# SolarPCB.net
KiCad netlist of a schematic drawn in Altium Designer
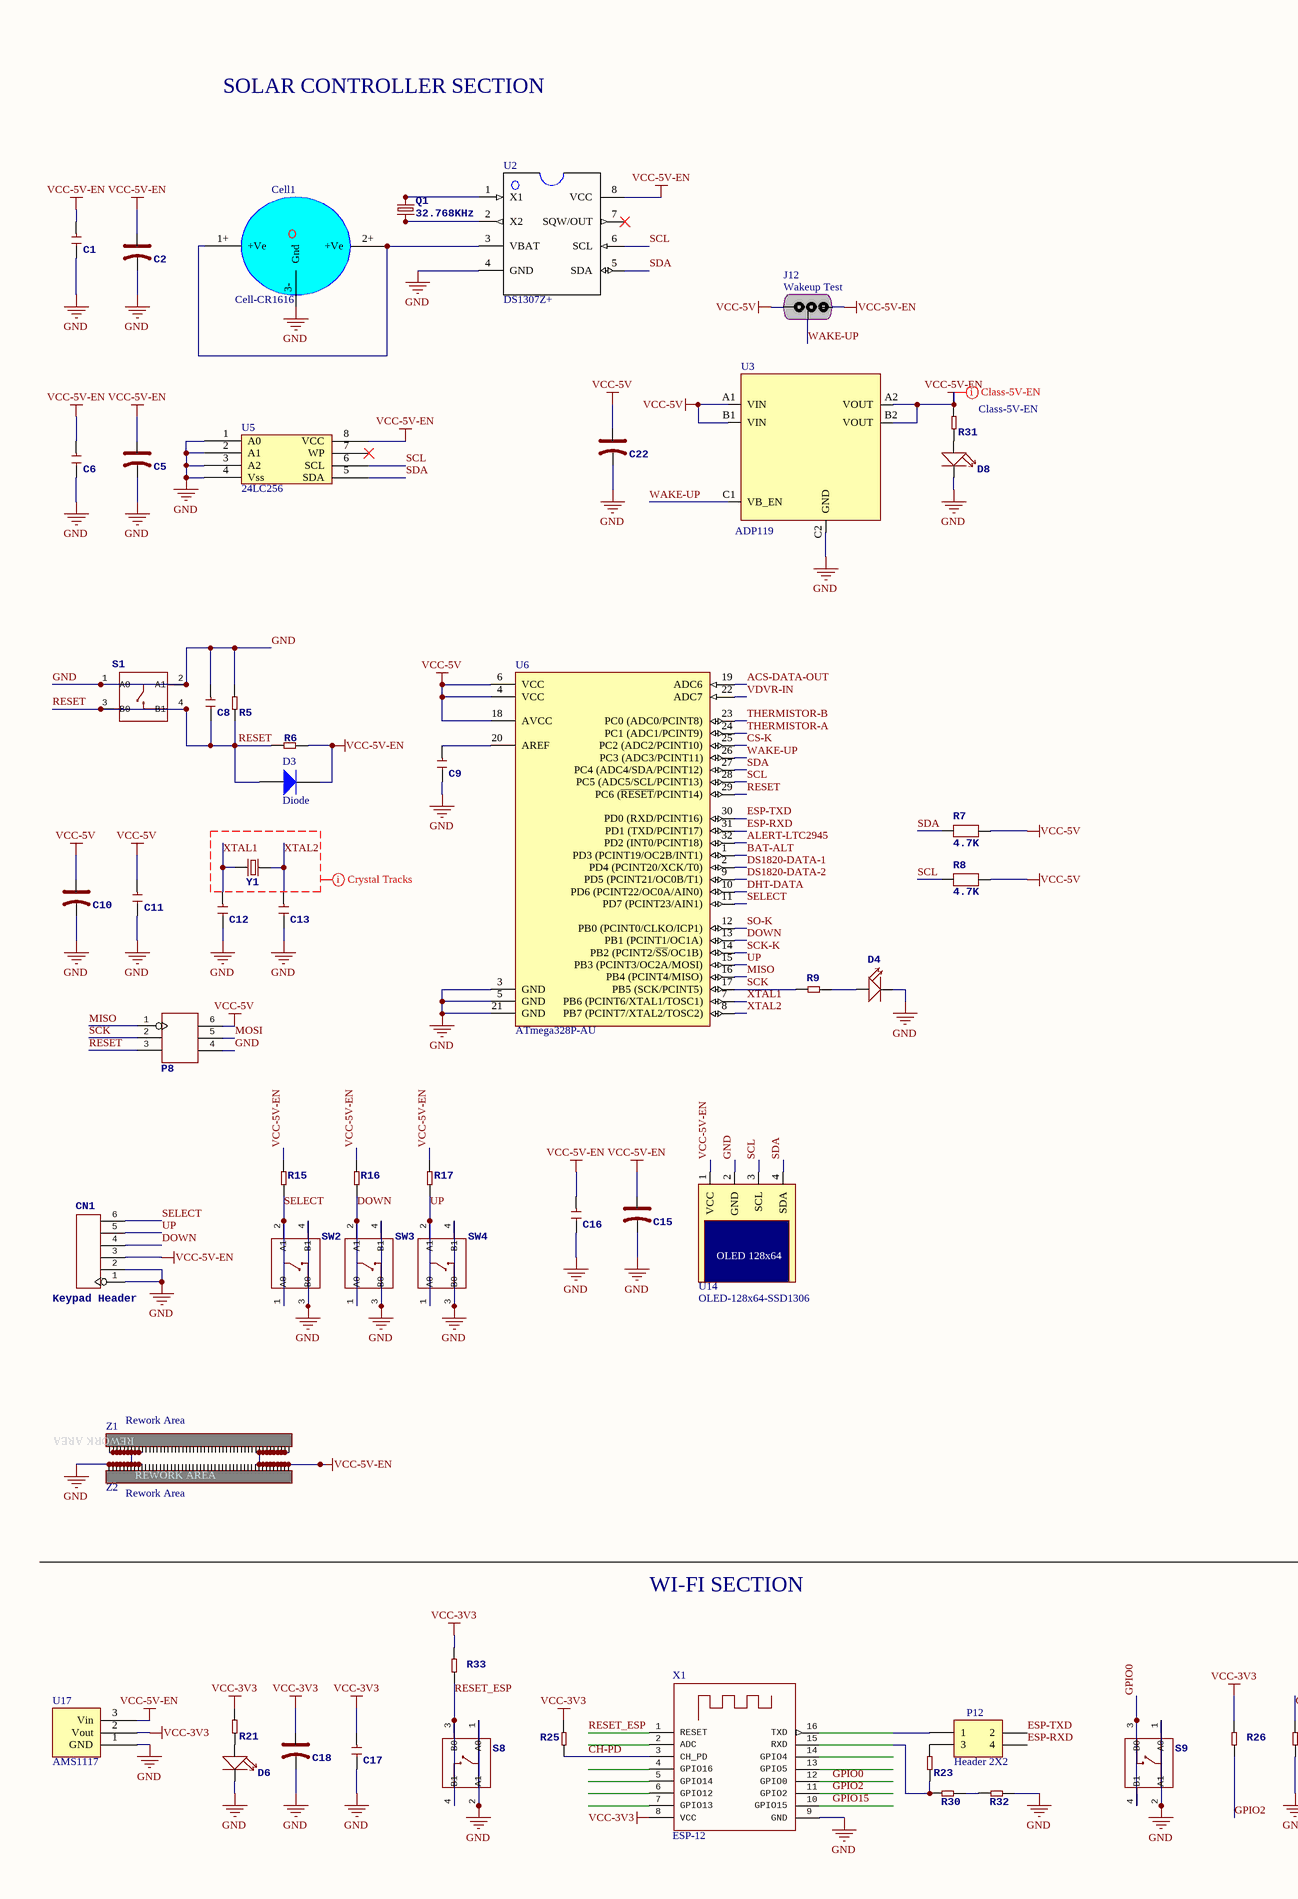
[diagram p0: SolarPCB.SchDoc, left]
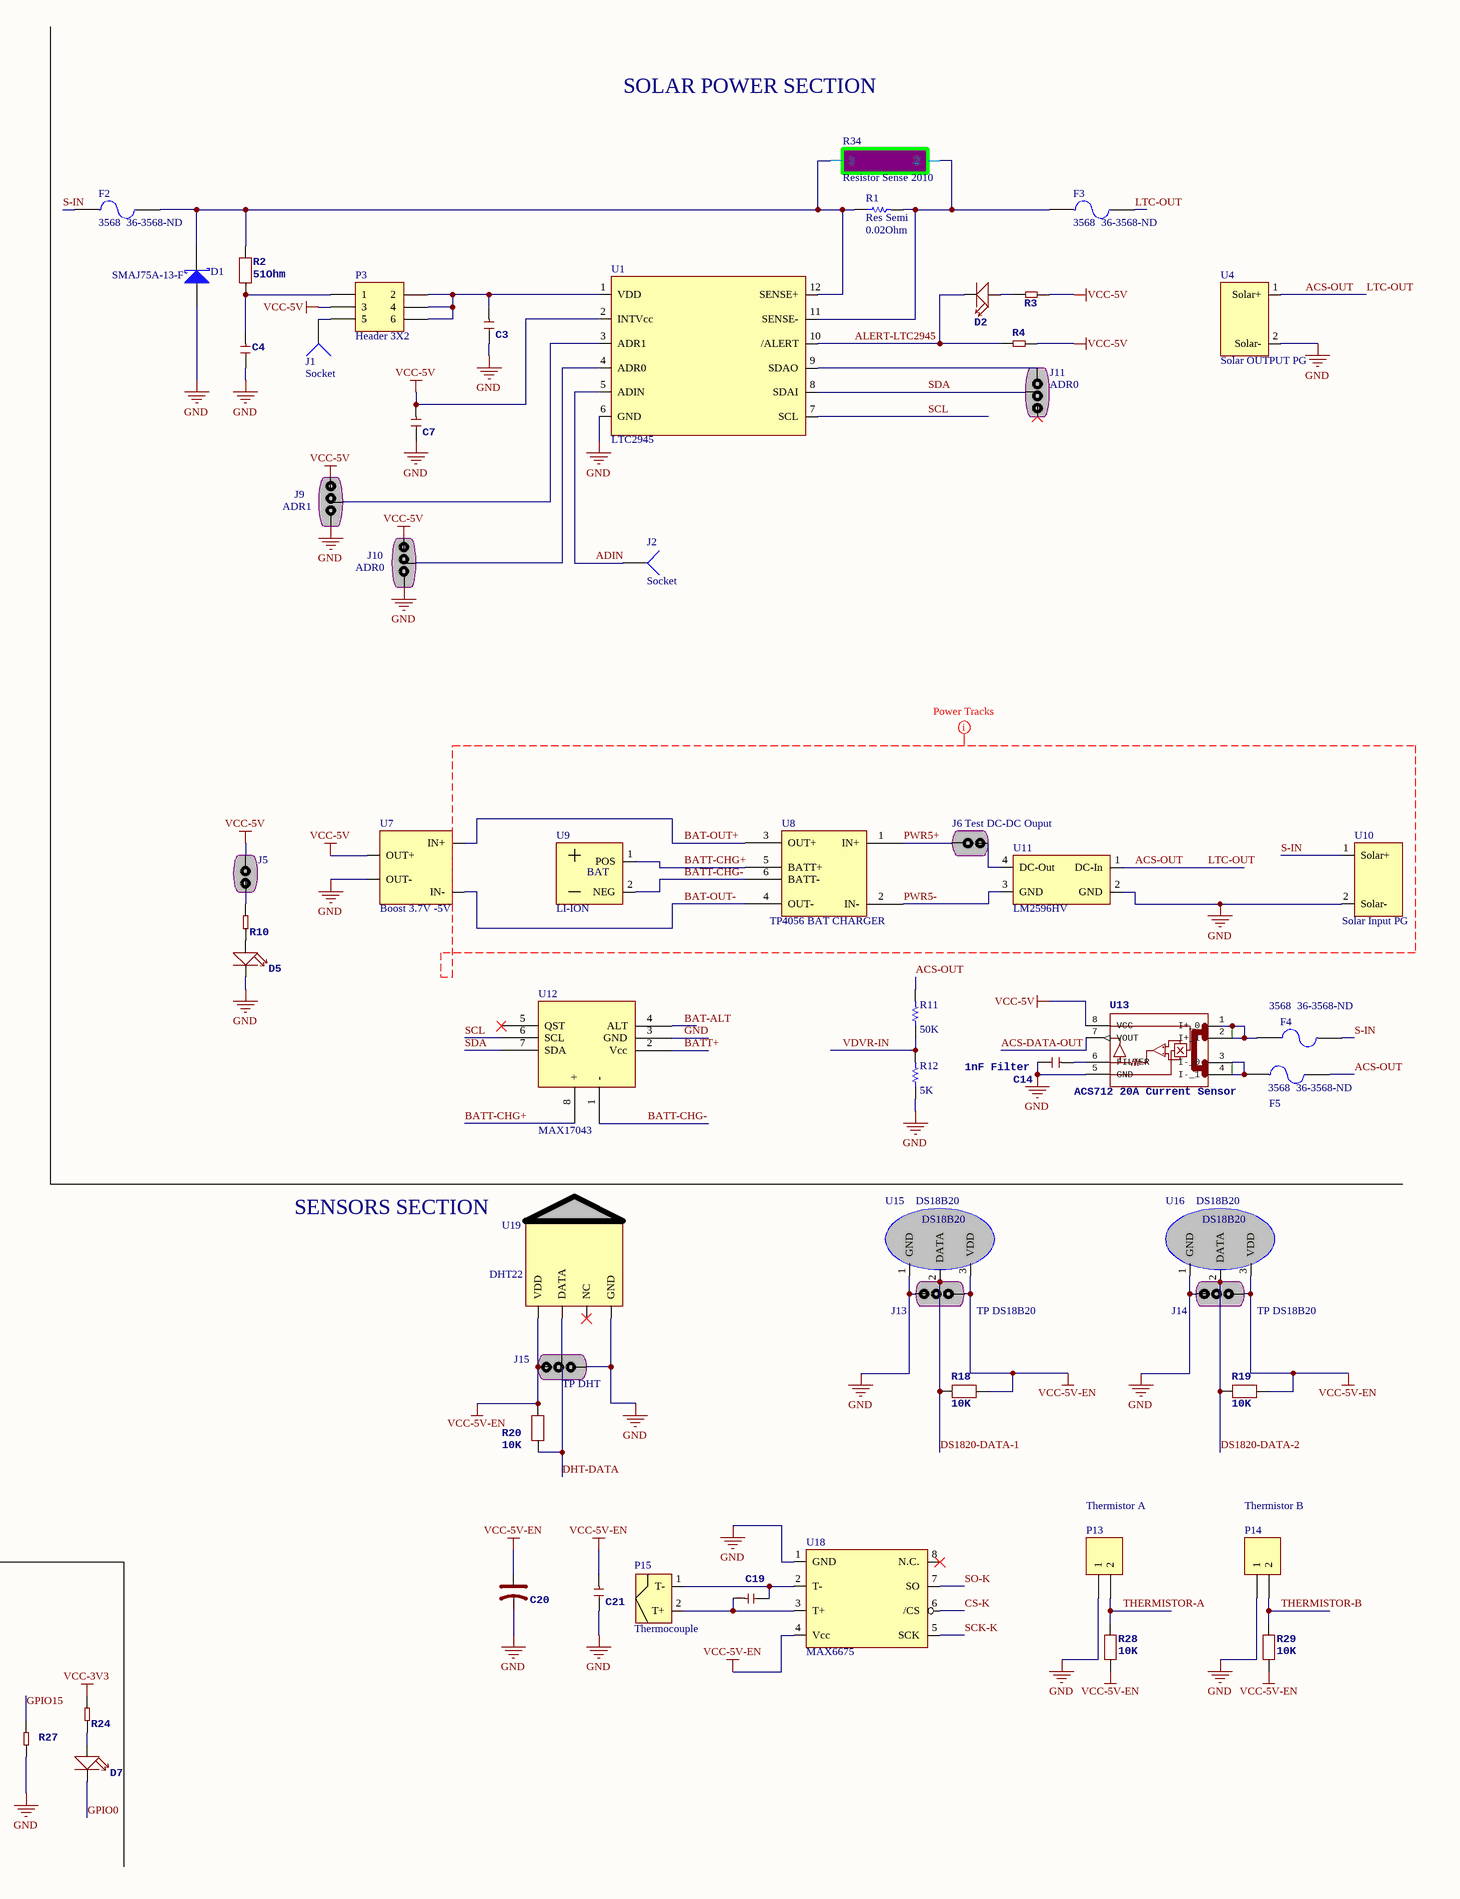
[diagram p1: SolarPCB.SchDoc, right]

(export (version "E")
  (design (tool "Eeschema 10.0.6"))
  (components
    (comp (ref "C1")
      (value "302010165")
      (footprint "C0805")
      (description "100nF")
      (fields (field (name "MPN") "CC0805KRX7R9BB104"))
      (libsource (lib "Seeed-Capacitor") (part "CERAMIC-100NF-50V-10%-X7R(0805)"))
    )
    (comp (ref "C2")
      (value "302020002")
      (footprint "AVX-A")
      (description "10uF Cap Decoupling 16V")
      (fields (field (name "MPN") "TAJA106K016RNJ"))
      (libsource (lib "Seeed-Capacitor") (part "TANTALUM-SMD-10UF-16V-10%(AVX-A)"))
    )
    (comp (ref "C3")
      (value "302010165")
      (footprint "C0805")
      (description "100nF")
      (fields (field (name "MPN") "CC0805KRX7R9BB104"))
      (libsource (lib "Seeed-Capacitor") (part "CERAMIC-100NF-50V-10%-X7R(0805)"))
    )
    (comp (ref "C4")
      (value "302010189")
      (footprint "C1206")
      (fields (field (name "MPN") "CC1206KKX7RCBB102"))
      (libsource (lib "Seeed-Capacitor") (part "CERAMIC-1NF-1KV-10%-X7R?(1206)"))
    )
    (comp (ref "C5")
      (value "302020002")
      (footprint "AVX-A")
      (description "10uF Cap Decoupling 16V")
      (fields (field (name "MPN") "TAJA106K016RNJ"))
      (libsource (lib "Seeed-Capacitor") (part "TANTALUM-SMD-10UF-16V-10%(AVX-A)"))
    )
    (comp (ref "C6")
      (value "302010165")
      (footprint "C0805")
      (description "100nF")
      (fields (field (name "MPN") "CC0805KRX7R9BB104"))
      (libsource (lib "Seeed-Capacitor") (part "CERAMIC-100NF-50V-10%-X7R(0805)"))
    )
    (comp (ref "C7")
      (value "302010165")
      (footprint "C0805")
      (description "100nF")
      (fields (field (name "MPN") "CC0805KRX7R9BB104"))
      (libsource (lib "Seeed-Capacitor") (part "CERAMIC-100NF-50V-10%-X7R(0805)"))
    )
    (comp (ref "C8")
      (value "302010165")
      (footprint "C0805")
      (description "100nF")
      (fields (field (name "MPN") "CC0805KRX7R9BB104"))
      (libsource (lib "Seeed-Capacitor") (part "CERAMIC-100NF-50V-10%-X7R(0805)"))
    )
    (comp (ref "C9")
      (value "302010165")
      (footprint "C0805")
      (description "100nF")
      (fields (field (name "MPN") "CC0805KRX7R9BB104"))
      (libsource (lib "Seeed-Capacitor") (part "CERAMIC-100NF-50V-10%-X7R(0805)"))
    )
    (comp (ref "C10")
      (value "302020002")
      (footprint "AVX-A")
      (description "10uF Cap Decoupling 16V")
      (fields (field (name "MPN") "TAJA106K016RNJ"))
      (libsource (lib "Seeed-Capacitor") (part "TANTALUM-SMD-10UF-16V-10%(AVX-A)"))
    )
    (comp (ref "C11")
      (value "302010165")
      (footprint "C0805")
      (description "100nF")
      (fields (field (name "MPN") "CC0805KRX7R9BB104"))
      (libsource (lib "Seeed-Capacitor") (part "CERAMIC-100NF-50V-10%-X7R(0805)"))
    )
    (comp (ref "C12")
      (value "302010018")
      (footprint "C0805")
      (fields (field (name "MPN") "CC0402JRNPO9BN220"))
      (libsource (lib "Seeed-Capacitor") (part "CERAMIC-22PF-50V-5%-NPO(0402)"))
    )
    (comp (ref "C13")
      (value "302010018")
      (footprint "C0805")
      (fields (field (name "MPN") "CC0402JRNPO9BN220"))
      (libsource (lib "Seeed-Capacitor") (part "CERAMIC-22PF-50V-5%-NPO(0402)"))
    )
    (comp (ref "C14")
      (value "1nF Filter")
      (footprint "C0805")
      (description "1nF Filter Cap as per Datasheet")
      (fields (field (name "MPN") "CC0402KRX7R8BB104"))
      (libsource (lib "Seeed-Capacitor") (part "CERAMIC-100NF-25V-10%-X7R(0402)"))
    )
    (comp (ref "C15")
      (value "302020002")
      (footprint "AVX-A")
      (description "10uF Cap Decoupling 16V")
      (fields (field (name "MPN") "TAJA106K016RNJ"))
      (libsource (lib "Seeed-Capacitor") (part "TANTALUM-SMD-10UF-16V-10%(AVX-A)"))
    )
    (comp (ref "C16")
      (value "302010165")
      (footprint "C0805")
      (description "100nF")
      (fields (field (name "MPN") "CC0805KRX7R9BB104"))
      (libsource (lib "Seeed-Capacitor") (part "CERAMIC-100NF-50V-10%-X7R(0805)"))
    )
    (comp (ref "C17")
      (value "302010165")
      (footprint "C0805")
      (description "100nF")
      (fields (field (name "MPN") "CC0805KRX7R9BB104"))
      (libsource (lib "Seeed-Capacitor") (part "CERAMIC-100NF-50V-10%-X7R(0805)"))
    )
    (comp (ref "C18")
      (value "302020002")
      (footprint "AVX-A")
      (description "10uF Cap Decoupling 16V")
      (fields (field (name "MPN") "TAJA106K016RNJ"))
      (libsource (lib "Seeed-Capacitor") (part "TANTALUM-SMD-10UF-16V-10%(AVX-A)"))
    )
    (comp (ref "C19")
      (value "302010175")
      (footprint "C0805")
      (fields (field (name "MPN") "CC0805JRX7R9BB103"))
      (libsource (lib "Seeed-Capacitor") (part "CERAMIC-10NF-50V-5%-X7R(0805)"))
    )
    (comp (ref "C20")
      (value "302020002")
      (footprint "AVX-A")
      (description "10uF Cap Decoupling 16V")
      (fields (field (name "MPN") "TAJA106K016RNJ"))
      (libsource (lib "Seeed-Capacitor") (part "TANTALUM-SMD-10UF-16V-10%(AVX-A)"))
    )
    (comp (ref "C21")
      (value "302010165")
      (footprint "C0805")
      (description "100nF")
      (fields (field (name "MPN") "CC0805KRX7R9BB104"))
      (libsource (lib "Seeed-Capacitor") (part "CERAMIC-100NF-50V-10%-X7R(0805)"))
    )
    (comp (ref "C22")
      (value "302020002")
      (footprint "AVX-A")
      (description "10uF Cap Decoupling 16V")
      (fields (field (name "MPN") "TAJA106K016RNJ"))
      (libsource (lib "Seeed-Capacitor") (part "TANTALUM-SMD-10UF-16V-10%(AVX-A)"))
    )
    (comp (ref "Cell1")
      (value "Cell-CR1616")
      (footprint "CellCR1616")
      (libsource (lib "Schlib_HAS_1.0") (part "Cell-CR1616"))
    )
    (comp (ref "CN1")
      (value "Keypad Header")
      (footprint "H6-2.54")
      (fields (field (name "MPN") "F185-1106A1BSYC1"))
      (libsource (lib "Seeed-Connector") (part "DIP-BLACK-FEMALE-HEADER-VERT(6P-2.54)"))
    )
    (comp (ref "D1")
      (value "SMAJ75A-13-F")
      (footprint "SMAJ5.0-TVS")
      (description "SMA")
      (fields (field (name "PUBLISHER") "Altium Limited"))
      (libsource (lib "Miscellaneous Devices") (part "D Schottky"))
    )
    (comp (ref "D2")
      (value "304090046")
      (footprint "LED-0805")
      (fields (field (name "MPN") "17-215SURC/S530-A2/TR8"))
      (libsource (lib "Seeed-LED") (part "SMD-LED-CLEAR-RED(0805)"))
    )
    (comp (ref "D3")
      (value "Diode")
      (footprint "1206 Diode SMD")
      (description "Default Diode")
      (fields (field (name "PUBLISHER") "Altium Limited"))
      (libsource (lib "Miscellaneous Devices") (part "Diode"))
    )
    (comp (ref "D4")
      (value "304090046")
      (footprint "LED-0805")
      (fields (field (name "MPN") "17-215SURC/S530-A2/TR8"))
      (libsource (lib "Seeed-LED") (part "SMD-LED-CLEAR-RED(0805)"))
    )
    (comp (ref "D5")
      (value "304090046")
      (footprint "LED-0805")
      (fields (field (name "MPN") "17-215SURC/S530-A2/TR8"))
      (libsource (lib "Seeed-LED") (part "SMD-LED-CLEAR-RED(0805)"))
    )
    (comp (ref "D6")
      (value "304090046")
      (footprint "LED-0805")
      (fields (field (name "MPN") "17-215SURC/S530-A2/TR8"))
      (libsource (lib "Seeed-LED") (part "SMD-LED-CLEAR-RED(0805)"))
    )
    (comp (ref "D7")
      (value "304090046")
      (footprint "LED-0805")
      (fields (field (name "MPN") "17-215SURC/S530-A2/TR8"))
      (libsource (lib "Seeed-LED") (part "SMD-LED-CLEAR-RED(0805)"))
    )
    (comp (ref "D8")
      (value "304090046")
      (footprint "LED-0805")
      (fields (field (name "MPN") "17-215SURC/S530-A2/TR8"))
      (libsource (lib "Seeed-LED") (part "SMD-LED-CLEAR-RED(0805)"))
    )
    (comp (ref "F2")
      (value "3568  36-3568-ND")
      (footprint "Fuse Holder Mini BLADE ATC")
      (description "3568  36-3568-ND FUSE HOLDER")
      (fields (field (name "PUBLISHER") "Altium Limited"))
      (libsource (lib "Miscellaneous Devices") (part "Fuse 2"))
    )
    (comp (ref "F3")
      (value "3568  36-3568-ND")
      (footprint "Fuse Holder Mini BLADE ATC")
      (description "3568  36-3568-ND FUSE HOLDER")
      (fields (field (name "PUBLISHER") "Altium Limited"))
      (libsource (lib "Miscellaneous Devices") (part "Fuse 2"))
    )
    (comp (ref "F4")
      (value "3568  36-3568-ND")
      (footprint "Fuse Holder Mini BLADE ATC")
      (description "3568  36-3568-ND FUSE HOLDER")
      (fields (field (name "PUBLISHER") "Altium Limited"))
      (libsource (lib "Miscellaneous Devices") (part "Fuse 2"))
    )
    (comp (ref "F5")
      (value "3568  36-3568-ND")
      (footprint "Fuse Holder Mini BLADE ATC")
      (description "3568  36-3568-ND FUSE HOLDER")
      (fields (field (name "PUBLISHER") "Altium Limited"))
      (libsource (lib "Miscellaneous Devices") (part "Fuse 2"))
    )
    (comp (ref "J1")
      (value "Socket")
      (footprint "PIN1")
      (fields (field (name "PUBLISHER") "Altium Limited"))
      (libsource (lib "Miscellaneous Connectors") (part "Socket"))
    )
    (comp (ref "J2")
      (value "Socket")
      (footprint "PIN1")
      (fields (field (name "PUBLISHER") "Altium Limited"))
      (libsource (lib "Miscellaneous Connectors") (part "Socket"))
    )
    (comp (ref "J5")
      (value "Jumper 2Pin")
      (footprint "H2-2.54")
      (description "2.54, Pin header")
      (libsource (lib "Solar_Schlib1") (part "Jumper"))
    )
    (comp (ref "J6")
      (value "Test DC-DC Ouput")
      (footprint "H2-2.54")
      (description "2.54, Pin header")
      (libsource (lib "Solar_Schlib1") (part "Jumper"))
    )
    (comp (ref "J9")
      (value "ADR1")
      (footprint "H3-2.54")
      (description "2.54mm Pitch male header")
      (libsource (lib "Solar_Schlib1") (part "Jumper Select"))
    )
    (comp (ref "J10")
      (value "ADR0")
      (footprint "H3-2.54")
      (description "2.54mm Pitch male header")
      (libsource (lib "Solar_Schlib1") (part "Jumper Select"))
    )
    (comp (ref "J11")
      (value "ADR0")
      (footprint "H3-2.54")
      (description "2.54mm Pitch male header")
      (libsource (lib "Solar_Schlib1") (part "Jumper Select"))
    )
    (comp (ref "J12")
      (value "Wakeup Test")
      (footprint "H3-2.54")
      (description "2.54mm Pitch male header")
      (libsource (lib "Solar_Schlib1") (part "Jumper Select"))
    )
    (comp (ref "J13")
      (value "TP DS18B20")
      (footprint "H3-2.54")
      (description "2.54mm Pitch male header")
      (libsource (lib "Solar_Schlib1") (part "Jumper Select"))
    )
    (comp (ref "J14")
      (value "TP DS18B20")
      (footprint "H3-2.54")
      (description "2.54mm Pitch male header")
      (libsource (lib "Solar_Schlib1") (part "Jumper Select"))
    )
    (comp (ref "J15")
      (value "TP DHT")
      (footprint "H3-2.54")
      (description "2.54mm Pitch male header")
      (libsource (lib "Solar_Schlib1") (part "Jumper Select"))
    )
    (comp (ref "P3")
      (value "Header 3X2")
      (footprint "HDR2X3")
      (description "Header, 3-Pin, Dual row")
      (fields (field (name "PUBLISHER") "Altium Limited"))
      (libsource (lib "Miscellaneous Connectors") (part "Header 3X2"))
    )
    (comp (ref "P8")
      (value "320020077")
      (footprint "HDR1X6")
      (fields (field (name "MPN") "P125-12A1BS116A1"))
      (libsource (lib "Seeed-Connector") (part "DIP-BLACK-MALE-HEADER(2X3P-2.54）-2.54"))
    )
    (comp (ref "P12")
      (value "Header 2X2")
      (footprint "HDR2X2")
      (description "Header, 2-Pin, Dual row")
      (fields (field (name "PUBLISHER") "Altium Limited"))
      (libsource (lib "Miscellaneous Connectors") (part "Header 2X2"))
    )
    (comp (ref "P13")
      (value "Thermistor A")
      (footprint "HDR1X2")
      (description "Header, 2-Pin")
      (fields (field (name "PUBLISHER") "Altium Limited"))
      (libsource (lib "Miscellaneous Connectors") (part "Header 2"))
    )
    (comp (ref "P14")
      (value "Thermistor B")
      (footprint "HDR1X2")
      (description "Header, 2-Pin")
      (fields (field (name "PUBLISHER") "Altium Limited"))
      (libsource (lib "Miscellaneous Connectors") (part "Header 2"))
    )
    (comp (ref "P15")
      (value "Thermocouple")
      (footprint "ScrewTerminal8.5")
      (description "K Type Termocouple")
      (libsource (lib "Solar_Schlib1") (part "ScrewTerminal8.5"))
    )
    (comp (ref "Q1")
      (value "32.768KHz")
      (footprint "RTC-XTAL")
      (libsource (lib "crystal") (part "CRYTALTC38H"))
    )
    (comp (ref "R1")
      (value "Res Semi")
      (footprint "AXIAL-0.5")
      (description "Semiconductor Resistor")
      (fields (field (name "ALTIUM_VALUE") "0.02Ohm") (field (name "PUBLISHER") "Altium Limited"))
      (libsource (lib "Miscellaneous Devices") (part "Res Semi"))
    )
    (comp (ref "R2")
      (value "51Ohm")
      (footprint "R0805")
      (libsource (lib "microbuilder") (part "RESISTOR0805_NOOUTLINE"))
    )
    (comp (ref "R3")
      (value "301010297")
      (footprint "R0603")
      (fields (field (name "MPN") "RC0603JR-07390RL"))
      (libsource (lib "Seeed-Resistor") (part "SMD-RES-390R-5%-1/10W(0603)"))
    )
    (comp (ref "R4")
      (value "301010361")
      (footprint "R0805")
      (description "10K")
      (fields (field (name "MPN") "RC0805FR-0710KL"))
      (libsource (lib "Seeed-Resistor") (part "SMD-RES-10K-1%-1/8W(0805)"))
    )
    (comp (ref "R5")
      (value "301010006")
      (footprint "R0402")
      (fields (field (name "MPN") "RC0402JR-071KL"))
      (libsource (lib "Seeed-Resistor") (part "SMD-RES-1K-5%-1/16W(0402)"))
    )
    (comp (ref "R6")
      (value "301010361")
      (footprint "R0805")
      (description "Pull up 10K resistor")
      (fields (field (name "MPN") "RC0805FR-0710KL"))
      (libsource (lib "Seeed-Resistor") (part "SMD-RES-10K-1%-1/8W(0805)"))
    )
    (comp (ref "R7")
      (value "4.7K")
      (footprint "R0805")
      (libsource (lib "microbuilder") (part "RESISTOR0805_NOOUTLINE"))
    )
    (comp (ref "R8")
      (value "4.7K")
      (footprint "R0805")
      (libsource (lib "microbuilder") (part "RESISTOR0805_NOOUTLINE"))
    )
    (comp (ref "R9")
      (value "301010297")
      (footprint "R0603")
      (fields (field (name "MPN") "RC0603JR-07390RL"))
      (libsource (lib "Seeed-Resistor") (part "SMD-RES-390R-5%-1/10W(0603)"))
    )
    (comp (ref "R10")
      (value "301010297")
      (footprint "R0603")
      (fields (field (name "MPN") "RC0603JR-07390RL"))
      (libsource (lib "Seeed-Resistor") (part "SMD-RES-390R-5%-1/10W(0603)"))
    )
    (comp (ref "R11")
      (value "50K")
      (footprint "AXIAL-0.3")
      (description "Resistor")
      (fields (field (name "PUBLISHER") "Altium Limited"))
      (libsource (lib "Miscellaneous Devices") (part "Res1"))
    )
    (comp (ref "R12")
      (value "5K")
      (footprint "AXIAL-0.3")
      (description "Resistor")
      (fields (field (name "PUBLISHER") "Altium Limited"))
      (libsource (lib "Miscellaneous Devices") (part "Res1"))
    )
    (comp (ref "R15")
      (value "301010361")
      (footprint "R0805")
      (description "Pull up 10K resistor for button")
      (fields (field (name "MPN") "RC0805FR-0710KL"))
      (libsource (lib "Seeed-Resistor") (part "SMD-RES-10K-1%-1/8W(0805)"))
    )
    (comp (ref "R16")
      (value "301010361")
      (footprint "R0805")
      (description "Pull up 10K resistor for button")
      (fields (field (name "MPN") "RC0805FR-0710KL"))
      (libsource (lib "Seeed-Resistor") (part "SMD-RES-10K-1%-1/8W(0805)"))
    )
    (comp (ref "R17")
      (value "301010361")
      (footprint "R0805")
      (description "Pull up 10K resistor for button")
      (fields (field (name "MPN") "RC0805FR-0710KL"))
      (libsource (lib "Seeed-Resistor") (part "SMD-RES-10K-1%-1/8W(0805)"))
    )
    (comp (ref "R18")
      (value "10K")
      (footprint "R0805")
      (libsource (lib "microbuilder") (part "RESISTOR0805_NOOUTLINE"))
    )
    (comp (ref "R19")
      (value "10K")
      (footprint "R0805")
      (libsource (lib "microbuilder") (part "RESISTOR0805_NOOUTLINE"))
    )
    (comp (ref "R20")
      (value "10K")
      (footprint "R0805")
      (libsource (lib "microbuilder") (part "RESISTOR0805_NOOUTLINE"))
    )
    (comp (ref "R21")
      (value "301010297")
      (footprint "R0603")
      (fields (field (name "MPN") "RC0603JR-07390RL"))
      (libsource (lib "Seeed-Resistor") (part "SMD-RES-390R-5%-1/10W(0603)"))
    )
    (comp (ref "R23")
      (value "301010311")
      (footprint "R0805")
      (fields (field (name "MPN") "RC0805JR-071KL"))
      (libsource (lib "Seeed-Resistor") (part "SMD-RES-1K-5%-1/8W(0805)"))
    )
    (comp (ref "R24")
      (value "301010297")
      (footprint "R0603")
      (fields (field (name "MPN") "RC0603JR-07390RL"))
      (libsource (lib "Seeed-Resistor") (part "SMD-RES-390R-5%-1/10W(0603)"))
    )
    (comp (ref "R25")
      (value "301010361")
      (footprint "R0805")
      (description "Pull up 10K resistor for button")
      (fields (field (name "MPN") "RC0805FR-0710KL"))
      (libsource (lib "Seeed-Resistor") (part "SMD-RES-10K-1%-1/8W(0805)"))
    )
    (comp (ref "R26")
      (value "301010361")
      (footprint "R0805")
      (description "Pull up 10K resistor for button")
      (fields (field (name "MPN") "RC0805FR-0710KL"))
      (libsource (lib "Seeed-Resistor") (part "SMD-RES-10K-1%-1/8W(0805)"))
    )
    (comp (ref "R27")
      (value "301010361")
      (footprint "R0805")
      (description "Pull up 10K resistor for button")
      (fields (field (name "MPN") "RC0805FR-0710KL"))
      (libsource (lib "Seeed-Resistor") (part "SMD-RES-10K-1%-1/8W(0805)"))
    )
    (comp (ref "R28")
      (value "10K")
      (footprint "R0805")
      (libsource (lib "microbuilder") (part "RESISTOR0805_NOOUTLINE"))
    )
    (comp (ref "R29")
      (value "10K")
      (footprint "R0805")
      (libsource (lib "microbuilder") (part "RESISTOR0805_NOOUTLINE"))
    )
    (comp (ref "R30")
      (value "301010311")
      (footprint "R0805")
      (fields (field (name "MPN") "RC0805JR-071KL"))
      (libsource (lib "Seeed-Resistor") (part "SMD-RES-1K-5%-1/8W(0805)"))
    )
    (comp (ref "R31")
      (value "301010297")
      (footprint "R0603")
      (fields (field (name "MPN") "RC0603JR-07390RL"))
      (libsource (lib "Seeed-Resistor") (part "SMD-RES-390R-5%-1/10W(0603)"))
    )
    (comp (ref "R32")
      (value "301010311")
      (footprint "R0805")
      (fields (field (name "MPN") "RC0805JR-071KL"))
      (libsource (lib "Seeed-Resistor") (part "SMD-RES-1K-5%-1/8W(0805)"))
    )
    (comp (ref "R33")
      (value "301010361")
      (footprint "R0805")
      (description "Pull up 10K resistor for button")
      (fields (field (name "MPN") "RC0805FR-0710KL"))
      (libsource (lib "Seeed-Resistor") (part "SMD-RES-10K-1%-1/8W(0805)"))
    )
    (comp (ref "R34")
      (value "Resistor Sense 2010")
      (footprint "Resistor Sense 2010")
      (description "0.02 Ohm Resistor Current Sense")
      (libsource (lib "Solar_Schlib1") (part "Resistor Sense 2010"))
    )
    (comp (ref "S1")
      (value "311020017")
      (footprint "SW4-SMD-5.2X5.2X1.5MM")
      (fields (field (name "MPN") "SKQGADE010"))
      (libsource (lib "Seeed-Switch") (part "SMD-BUTTON(4P-5.2X5.2X1.5MM-SKQGADE010)-SKQGADE010"))
    )
    (comp (ref "S8")
      (value "311020017")
      (footprint "SW4-SMD-5.2X5.2X1.5MM")
      (fields (field (name "MPN") "SKQGADE010"))
      (libsource (lib "SolarPCB2.0") (part "SMD-BUTTON(4P-5.2X5.2X1.5MM-SKQGADE010)-SKQGADE010"))
    )
    (comp (ref "S9")
      (value "311020017")
      (footprint "SW4-SMD-5.2X5.2X1.5MM")
      (fields (field (name "MPN") "SKQGADE010"))
      (libsource (lib "SolarPCB2.0") (part "SMD-BUTTON(4P-5.2X5.2X1.5MM-SKQGADE010)-SKQGADE010"))
    )
    (comp (ref "SW2")
      (value "311020045")
      (footprint "SW4-SMD-4.2X3.2X2.5MM")
      (fields (field (name "MPN") "DHT-4235A"))
      (libsource (lib "Seeed-Switch") (part "SMD-BUTTON-TOP-DHT-4235A(4P-4.2X3.2MM)"))
    )
    (comp (ref "SW3")
      (value "311020045")
      (footprint "SW4-SMD-4.2X3.2X2.5MM")
      (fields (field (name "MPN") "DHT-4235A"))
      (libsource (lib "Seeed-Switch") (part "SMD-BUTTON-TOP-DHT-4235A(4P-4.2X3.2MM)"))
    )
    (comp (ref "SW4")
      (value "311020045")
      (footprint "SW4-SMD-4.2X3.2X2.5MM")
      (fields (field (name "MPN") "DHT-4235A"))
      (libsource (lib "Seeed-Switch") (part "SMD-BUTTON-TOP-DHT-4235A(4P-4.2X3.2MM)"))
    )
    (comp (ref "U1")
      (value "LTC2945")
      (footprint "LTC2945")
      (description "V I P Monitor I2C Interface")
      (libsource (lib "Solar_Schlib1") (part "LTC2945"))
    )
    (comp (ref "U2")
      (value "DS1307Z+")
      (footprint "SO08")
      (description "RTC circuit%3B I2C%3B NV SRAM%3B 56B%3B 4.5%C3%B75.5VDC%3B SO8")
      (fields (field (name "MF") "Maxim Integrated"))
      (libsource (lib "DS1307Z_") (part "DS1307Z+"))
    )
    (comp (ref "U3") (value "ADP119") (footprint "BGA3x2") (libsource (lib "Solar_Schlib1") (part "ADP119")))
    (comp (ref "U4") (value "Solar OUTPUT PG") (footprint "KF128-2P") (libsource (lib "") (part "PG_IN_1")))
    (comp (ref "U5") (value "24LC256") (footprint "SO08") (libsource (lib "Schlib_HAS_1.0") (part "24LC256")))
    (comp (ref "U6")
      (value "ATmega328P-AU")
      (footprint "TQFP32-0.8-7X7MM")
      (fields (field (name "PUBLISHER") "Altium Limited"))
      (libsource (lib "Atmel Microcontroller 8-Bit megaAVR") (part "ATmega328P-AU"))
    )
    (comp (ref "U7")
      (value "Boost 3.7V -5V")
      (footprint "Boost Cov")
      (description "Boost converter module from Cell to 5V")
      (libsource (lib "Solar_Schlib1") (part "Boost-3.7V-5V"))
    )
    (comp (ref "U8")
      (value "TP4056 BAT CHARGER")
      (footprint "TP4056")
      (description "TP4056 Module")
      (libsource (lib "eSizeSchLIB") (part "TP4056"))
    )
    (comp (ref "U9")
      (value "LI-ION")
      (footprint "Cell-Holder")
      (description "Li Ion Battery 3.7V")
      (libsource (lib "Solar_Schlib1") (part "Battery"))
    )
    (comp (ref "U10")
      (value "Solar Input PG")
      (footprint "KF128-2P")
      (libsource (lib "Solar_Schlib1") (part "PG_IN"))
    )
    (comp (ref "U11")
      (value "LM2596HV")
      (footprint "LM2596HVS DC-DC step-down module")
      (description "DC DC Adjustable Buck converter input upto 60V")
      (libsource (lib "Solar_Schlib1") (part "LM2596HV"))
    )
    (comp (ref "U12")
      (value "MAX17043")
      (footprint "MAX17043")
      (description "Battery Fuel Guage")
      (libsource (lib "eSizeSchLIB") (part "MAX17043"))
    )
    (comp (ref "U13")
      (value "ACS712 20A Current Sensor")
      (footprint "SO08")
      (libsource (lib "ACS712") (part "ACS712"))
    )
    (comp (ref "U14")
      (value "OLED-128x64-SSD1306")
      (footprint "OLED-128x64")
      (description "OLED Display OLED-128x64-SSD1306")
      (libsource (lib "Solar_Schlib1") (part "OLED-128x64-SSD1306"))
    )
    (comp (ref "U15")
      (value "DS18B20")
      (footprint "TO-92")
      (description "On Board Temperature Sensor")
      (libsource (lib "Solar_Schlib1") (part "DS18B20"))
    )
    (comp (ref "U16")
      (value "DS18B20")
      (footprint "TO-92")
      (description "On Board Temperature Sensor")
      (libsource (lib "Solar_Schlib1") (part "DS18B20"))
    )
    (comp (ref "U17")
      (value "AMS1117")
      (footprint "AMS1117-3.3")
      (description "3.3V Regulator")
      (libsource (lib "eSizeSchLIB") (part "AMS1117"))
    )
    (comp (ref "U18")
      (value "MAX6675")
      (description "K-Thermocoupleto-Digital  Converter")
      (libsource (lib "Solar_Schlib1") (part "MAX6675"))
    )
    (comp (ref "U19")
      (value "DHT22")
      (footprint "DHT22_AM2303_HORIZ")
      (description "Temperature and Humidity Sensor")
      (libsource (lib "Solar_Schlib1") (part "DHT22"))
    )
    (comp (ref "X1") (value "ESP-12") (footprint "ESP-12") (libsource (lib "adafruit") (part "ESP-12")))
    (comp (ref "Y1")
      (value "306010054")
      (footprint "SMT_XTAL")
      (fields (field (name "MPN") "X053201602002"))
      (libsource (lib "Seeed-Crystal Oscillator") (part "SMD-CRYSTAL-16MHZ-8PF-20PPM-40R(2P-5.0X3.2MM)"))
    )
    (comp (ref "Z1")
      (value "Rework Area")
      (footprint "Rework")
      (libsource (lib "Solar_Schlib1") (part "Rework Area"))
    )
    (comp (ref "Z2") (value "Rework Area") (footprint "Rework") (libsource (lib "") (part "Rework Area_1")))
  )
  (nets
    (net (code "1") (name "/ACS-DATA-OUT") (class "Default")
      (node (ref "U13") (pin "7") (pinfunction "VOUT_7") (pintype "output"))
      (node (ref "U6") (pin "19") (pinfunction "ADC6_19") (pintype "input"))
    )
    (net (code "2") (name "/ACS-OUT") (class "Default")
      (node (ref "F3") (pin "2") (pinfunction "2_2") (pintype "passive"))
      (node (ref "F5") (pin "2") (pinfunction "2_2") (pintype "passive"))
      (node (ref "R11") (pin "2") (pinfunction "2_2") (pintype "passive"))
      (node (ref "U11") (pin "1") (pinfunction "DC-In_1") (pintype "power_in"))
      (node (ref "U4") (pin "1") (pinfunction "Solar+_1") (pintype "power_in"))
    )
    (net (code "3") (name "/ADIN") (class "Default")
      (node (ref "J2") (pin "1") (pinfunction "1_1") (pintype "passive"))
      (node (ref "U1") (pin "5") (pinfunction "ADIN_5") (pintype "power_in"))
    )
    (net (code "4") (name "/ALERT-LTC2945") (class "Default")
      (node (ref "D2") (pin "-") (pinfunction "-_-") (pintype "passive"))
      (node (ref "R4") (pin "1") (pinfunction "1_1") (pintype "passive"))
      (node (ref "U1") (pin "10") (pinfunction "/ALERT_10") (pintype "power_in"))
      (node (ref "U6") (pin "32") (pinfunction "PD2_(INT0/PCINT18)_32") (pintype "bidirectional"))
    )
    (net (code "5") (name "/BAT-ALT") (class "Default")
      (node (ref "U12") (pin "4") (pinfunction "ALT_4") (pintype "passive"))
      (node (ref "U6") (pin "1") (pinfunction "PD3_(PCINT19/OC2B/INT1)_1") (pintype "bidirectional"))
    )
    (net (code "6") (name "/BAT-OUT+") (class "Default")
      (node (ref "U7") (pin "IN+") (pinfunction "IN+_IN+") (pintype "power_in"))
      (node (ref "U8") (pin "3") (pinfunction "OUT+_3") (pintype "power_in"))
    )
    (net (code "7") (name "/BAT-OUT-") (class "Default")
      (node (ref "U7") (pin "IN-") (pinfunction "IN-_IN-") (pintype "power_in"))
      (node (ref "U8") (pin "4") (pinfunction "OUT-_4") (pintype "power_in"))
    )
    (net (code "8") (name "/BATT+") (class "Default")
      (node (ref "U12") (pin "2") (pinfunction "Vcc_2") (pintype "passive"))
    )
    (net (code "9") (name "/BATT-CHG+") (class "Default")
      (node (ref "U12") (pin "8") (pinfunction "+_8") (pintype "passive"))
      (node (ref "U8") (pin "5") (pinfunction "BATT+_5") (pintype "power_in"))
      (node (ref "U9") (pin "1") (pinfunction "POS_1") (pintype "power_in"))
    )
    (net (code "10") (name "/BATT-CHG-") (class "Default")
      (node (ref "U12") (pin "1") (pinfunction "-_1") (pintype "passive"))
      (node (ref "U8") (pin "6") (pinfunction "BATT-_6") (pintype "power_in"))
      (node (ref "U9") (pin "2") (pinfunction "NEG_2") (pintype "power_in"))
    )
    (net (code "11") (name "/CH-PD") (class "Default")
      (node (ref "R25") (pin "1") (pinfunction "1_1") (pintype "passive"))
      (node (ref "X1") (pin "3") (pinfunction "CH_PD_3") (pintype "passive"))
    )
    (net (code "12") (name "/CS-K") (class "Default")
      (node (ref "U18") (pin "6") (pinfunction "/CS_6") (pintype "power_in"))
      (node (ref "U6") (pin "25") (pinfunction "PC2_(ADC2/PCINT10)_25") (pintype "bidirectional"))
    )
    (net (code "13") (name "/DHT-DATA") (class "Default")
      (node (ref "R20") (pin "1") (pinfunction "1_1") (pintype "passive"))
      (node (ref "U6") (pin "10") (pinfunction "PD6_(PCINT22/OC0A/AIN0)_10") (pintype "bidirectional"))
    )
    (net (code "14") (name "/DOWN") (class "Default")
      (node (ref "CN1") (pin "4") (pinfunction "4_4") (pintype "passive"))
      (node (ref "R16") (pin "1") (pinfunction "1_1") (pintype "passive"))
      (node (ref "SW3") (pin "1") (pinfunction "A0_1") (pintype "passive"))
      (node (ref "SW3") (pin "2") (pinfunction "A1_2") (pintype "passive"))
      (node (ref "U6") (pin "13") (pinfunction "PB1_(PCINT1/OC1A)_13") (pintype "bidirectional"))
    )
    (net (code "15") (name "/DS1820-DATA-1") (class "Default")
      (node (ref "J13") (pin "2") (pinfunction "2_2") (pintype "power_in"))
      (node (ref "R18") (pin "2") (pinfunction "2_2") (pintype "passive"))
      (node (ref "U15") (pin "2") (pinfunction "DATA_2") (pintype "power_in"))
      (node (ref "U6") (pin "2") (pinfunction "PD4_(PCINT20/XCK/T0)_2") (pintype "bidirectional"))
    )
    (net (code "16") (name "/DS1820-DATA-2") (class "Default")
      (node (ref "J14") (pin "2") (pinfunction "2_2") (pintype "power_in"))
      (node (ref "R19") (pin "2") (pinfunction "2_2") (pintype "passive"))
      (node (ref "U16") (pin "2") (pinfunction "DATA_2") (pintype "power_in"))
      (node (ref "U6") (pin "9") (pinfunction "PD5_(PCINT21/OC0B/T1)_9") (pintype "bidirectional"))
    )
    (net (code "17") (name "/ESP-RXD") (class "Default")
      (node (ref "P12") (pin "4") (pinfunction "4_4") (pintype "passive"))
      (node (ref "U6") (pin "31") (pinfunction "PD1_(TXD/PCINT17)_31") (pintype "bidirectional"))
    )
    (net (code "18") (name "/ESP-TXD") (class "Default")
      (node (ref "P12") (pin "2") (pinfunction "2_2") (pintype "passive"))
      (node (ref "U6") (pin "30") (pinfunction "PD0_(RXD/PCINT16)_30") (pintype "bidirectional"))
    )
    (net (code "19") (name "/GPIO0") (class "Default")
      (node (ref "D7") (pin "-") (pinfunction "-_-") (pintype "passive"))
      (node (ref "S9") (pin "3") (pinfunction "B0_3") (pintype "passive"))
      (node (ref "S9") (pin "4") (pinfunction "B1_4") (pintype "passive"))
      (node (ref "X1") (pin "12") (pinfunction "GPIO0_12") (pintype "passive"))
    )
    (net (code "20") (name "/GPIO2") (class "Default")
      (node (ref "R26") (pin "1") (pinfunction "1_1") (pintype "passive"))
      (node (ref "X1") (pin "11") (pinfunction "GPIO2_11") (pintype "passive"))
    )
    (net (code "21") (name "/GPIO15") (class "Default")
      (node (ref "R27") (pin "2") (pinfunction "2_2") (pintype "passive"))
      (node (ref "X1") (pin "10") (pinfunction "GPIO15_10") (pintype "passive"))
    )
    (net (code "22") (name "/MISO") (class "Default")
      (node (ref "P8") (pin "1") (pinfunction "1_1") (pintype "passive"))
      (node (ref "U6") (pin "16") (pinfunction "PB4_(PCINT4/MISO)_16") (pintype "bidirectional"))
    )
    (net (code "23") (name "/MOSI") (class "Default")
      (node (ref "P8") (pin "5") (pinfunction "5_5") (pintype "passive"))
    )
    (net (code "24") (name "/PWR5+") (class "Default")
      (node (ref "J6") (pin "2") (pinfunction "2_2") (pintype "power_in"))
      (node (ref "U8") (pin "1") (pinfunction "IN+_1") (pintype "power_in"))
    )
    (net (code "25") (name "/PWR5-") (class "Default")
      (node (ref "U11") (pin "3") (pinfunction "GND_3") (pintype "power_in"))
      (node (ref "U8") (pin "2") (pinfunction "IN-_2") (pintype "power_in"))
    )
    (net (code "26") (name "/RESET") (class "Default")
      (node (ref "C8") (pin "1") (pinfunction "1_1") (pintype "passive"))
      (node (ref "D3") (pin "1") (pinfunction "A_1") (pintype "passive"))
      (node (ref "P8") (pin "3") (pinfunction "3_3") (pintype "passive"))
      (node (ref "R5") (pin "2") (pinfunction "2_2") (pintype "passive"))
      (node (ref "R6") (pin "2") (pinfunction "2_2") (pintype "passive"))
      (node (ref "S1") (pin "3") (pinfunction "B0_3") (pintype "passive"))
      (node (ref "S1") (pin "4") (pinfunction "B1_4") (pintype "passive"))
      (node (ref "U6") (pin "29") (pinfunction "PC6_(~{RESET}/PCINT14)_29") (pintype "bidirectional"))
    )
    (net (code "27") (name "/RESET_ESP") (class "Default")
      (node (ref "R33") (pin "1") (pinfunction "1_1") (pintype "passive"))
      (node (ref "S8") (pin "3") (pinfunction "B0_3") (pintype "passive"))
      (node (ref "S8") (pin "4") (pinfunction "B1_4") (pintype "passive"))
      (node (ref "X1") (pin "1") (pinfunction "RESET_1") (pintype "passive"))
    )
    (net (code "28") (name "/S-IN") (class "Default")
      (node (ref "F2") (pin "1") (pinfunction "1_1") (pintype "passive"))
      (node (ref "F4") (pin "1") (pinfunction "1_1") (pintype "passive"))
      (node (ref "U10") (pin "1") (pinfunction "Solar+_1") (pintype "power_in"))
    )
    (net (code "29") (name "/SCK") (class "Default")
      (node (ref "P8") (pin "2") (pinfunction "2_2") (pintype "passive"))
      (node (ref "R9") (pin "1") (pinfunction "1_1") (pintype "passive"))
      (node (ref "U6") (pin "17") (pinfunction "PB5_(SCK/PCINT5)_17") (pintype "bidirectional"))
    )
    (net (code "30") (name "/SCK-K") (class "Default")
      (node (ref "U18") (pin "5") (pinfunction "SCK_5") (pintype "power_in"))
      (node (ref "U6") (pin "14") (pinfunction "PB2_(PCINT2/~{SS}/OC1B)_14") (pintype "bidirectional"))
    )
    (net (code "31") (name "/SCL") (class "Default")
      (node (ref "R8") (pin "1") (pinfunction "1_1") (pintype "passive"))
      (node (ref "U1") (pin "7") (pinfunction "SCL_7") (pintype "power_in"))
      (node (ref "U12") (pin "6") (pinfunction "SCL_6") (pintype "passive"))
      (node (ref "U14") (pin "3") (pinfunction "SCL_3") (pintype "power_in"))
      (node (ref "U2") (pin "6") (pinfunction "SCL_6") (pintype "input"))
      (node (ref "U5") (pin "6") (pinfunction "SCL_6") (pintype "passive"))
      (node (ref "U6") (pin "28") (pinfunction "PC5_(ADC5/SCL/PCINT13)_28") (pintype "bidirectional"))
    )
    (net (code "32") (name "/SDA") (class "Default")
      (node (ref "J11") (pin "2") (pinfunction "2_2") (pintype "power_in"))
      (node (ref "R7") (pin "1") (pinfunction "1_1") (pintype "passive"))
      (node (ref "U1") (pin "8") (pinfunction "SDAI_8") (pintype "power_in"))
      (node (ref "U12") (pin "7") (pinfunction "SDA_7") (pintype "passive"))
      (node (ref "U14") (pin "4") (pinfunction "SDA_4") (pintype "power_in"))
      (node (ref "U2") (pin "5") (pinfunction "SDA_5") (pintype "bidirectional"))
      (node (ref "U5") (pin "5") (pinfunction "SDA_5") (pintype "passive"))
      (node (ref "U6") (pin "27") (pinfunction "PC4_(ADC4/SDA/PCINT12)_27") (pintype "bidirectional"))
    )
    (net (code "33") (name "/SELECT") (class "Default")
      (node (ref "CN1") (pin "6") (pinfunction "6_6") (pintype "passive"))
      (node (ref "R15") (pin "1") (pinfunction "1_1") (pintype "passive"))
      (node (ref "SW2") (pin "1") (pinfunction "A0_1") (pintype "passive"))
      (node (ref "SW2") (pin "2") (pinfunction "A1_2") (pintype "passive"))
      (node (ref "U6") (pin "11") (pinfunction "PD7_(PCINT23/AIN1)_11") (pintype "bidirectional"))
    )
    (net (code "34") (name "/SO-K") (class "Default")
      (node (ref "U18") (pin "7") (pinfunction "SO_7") (pintype "power_in"))
      (node (ref "U6") (pin "12") (pinfunction "PB0_(PCINT0/CLKO/ICP1)_12") (pintype "bidirectional"))
    )
    (net (code "35") (name "/THERMISTOR-A") (class "Default")
      (node (ref "P13") (pin "2") (pinfunction "2_2") (pintype "passive"))
      (node (ref "R28") (pin "2") (pinfunction "2_2") (pintype "passive"))
      (node (ref "U6") (pin "24") (pinfunction "PC1_(ADC1/PCINT9)_24") (pintype "bidirectional"))
    )
    (net (code "36") (name "/THERMISTOR-B") (class "Default")
      (node (ref "P14") (pin "2") (pinfunction "2_2") (pintype "passive"))
      (node (ref "R29") (pin "2") (pinfunction "2_2") (pintype "passive"))
      (node (ref "U6") (pin "23") (pinfunction "PC0_(ADC0/PCINT8)_23") (pintype "bidirectional"))
    )
    (net (code "37") (name "/UP") (class "Default")
      (node (ref "CN1") (pin "5") (pinfunction "5_5") (pintype "passive"))
      (node (ref "R17") (pin "1") (pinfunction "1_1") (pintype "passive"))
      (node (ref "SW4") (pin "1") (pinfunction "A0_1") (pintype "passive"))
      (node (ref "SW4") (pin "2") (pinfunction "A1_2") (pintype "passive"))
      (node (ref "U6") (pin "15") (pinfunction "PB3_(PCINT3/OC2A/MOSI)_15") (pintype "bidirectional"))
    )
    (net (code "38") (name "/VDVR-IN") (class "Default")
      (node (ref "R11") (pin "1") (pinfunction "1_1") (pintype "passive"))
      (node (ref "R12") (pin "2") (pinfunction "2_2") (pintype "passive"))
      (node (ref "U6") (pin "22") (pinfunction "ADC7_22") (pintype "input"))
    )
    (net (code "39") (name "/WAKE-UP") (class "Default")
      (node (ref "J12") (pin "2") (pinfunction "2_2") (pintype "power_in"))
      (node (ref "U3") (pin "C1") (pinfunction "VB_EN_C1") (pintype "power_in"))
      (node (ref "U6") (pin "26") (pinfunction "PC3_(ADC3/PCINT11)_26") (pintype "bidirectional"))
    )
    (net (code "40") (name "/XTAL1") (class "Default")
      (node (ref "C12") (pin "2") (pinfunction "2_2") (pintype "passive"))
      (node (ref "U6") (pin "7") (pinfunction "PB6_(PCINT6/XTAL1/TOSC1)_7") (pintype "bidirectional"))
      (node (ref "Y1") (pin "1") (pinfunction "1_1") (pintype "passive"))
    )
    (net (code "41") (name "/XTAL2") (class "Default")
      (node (ref "C13") (pin "2") (pinfunction "2_2") (pintype "passive"))
      (node (ref "U6") (pin "8") (pinfunction "PB7_(PCINT7/XTAL2/TOSC2)_8") (pintype "bidirectional"))
      (node (ref "Y1") (pin "2") (pinfunction "2_2") (pintype "passive"))
    )
    (net (code "42") (name "GND") (class "Default")
      (node (ref "C1") (pin "1") (pinfunction "1_1") (pintype "passive"))
      (node (ref "C10") (pin "-") (pinfunction "-_-") (pintype "passive"))
      (node (ref "C11") (pin "1") (pinfunction "1_1") (pintype "passive"))
      (node (ref "C12") (pin "1") (pinfunction "1_1") (pintype "passive"))
      (node (ref "C13") (pin "1") (pinfunction "1_1") (pintype "passive"))
      (node (ref "C14") (pin "1") (pinfunction "1_1") (pintype "passive"))
      (node (ref "C15") (pin "-") (pinfunction "-_-") (pintype "passive"))
      (node (ref "C16") (pin "1") (pinfunction "1_1") (pintype "passive"))
      (node (ref "C17") (pin "1") (pinfunction "1_1") (pintype "passive"))
      (node (ref "C18") (pin "-") (pinfunction "-_-") (pintype "passive"))
      (node (ref "C2") (pin "-") (pinfunction "-_-") (pintype "passive"))
      (node (ref "C20") (pin "-") (pinfunction "-_-") (pintype "passive"))
      (node (ref "C21") (pin "1") (pinfunction "1_1") (pintype "passive"))
      (node (ref "C22") (pin "-") (pinfunction "-_-") (pintype "passive"))
      (node (ref "C3") (pin "1") (pinfunction "1_1") (pintype "passive"))
      (node (ref "C4") (pin "1") (pinfunction "1_1") (pintype "passive"))
      (node (ref "C5") (pin "-") (pinfunction "-_-") (pintype "passive"))
      (node (ref "C6") (pin "1") (pinfunction "1_1") (pintype "passive"))
      (node (ref "C7") (pin "1") (pinfunction "1_1") (pintype "passive"))
      (node (ref "C8") (pin "2") (pinfunction "2_2") (pintype "passive"))
      (node (ref "C9") (pin "1") (pinfunction "1_1") (pintype "passive"))
      (node (ref "CN1") (pin "1") (pinfunction "1_1") (pintype "passive"))
      (node (ref "CN1") (pin "2") (pinfunction "2_2") (pintype "passive"))
      (node (ref "Cell1") (pin "3-") (pinfunction "Gnd_3-") (pintype "passive"))
      (node (ref "D1") (pin "1") (pinfunction "A_1") (pintype "passive"))
      (node (ref "D4") (pin "-") (pinfunction "-_-") (pintype "passive"))
      (node (ref "D5") (pin "-") (pinfunction "-_-") (pintype "passive"))
      (node (ref "D6") (pin "-") (pinfunction "-_-") (pintype "passive"))
      (node (ref "D8") (pin "-") (pinfunction "-_-") (pintype "passive"))
      (node (ref "J10") (pin "1") (pintype "power_in"))
      (node (ref "J13") (pin "3") (pinfunction "3_3") (pintype "power_in"))
      (node (ref "J14") (pin "3") (pinfunction "3_3") (pintype "power_in"))
      (node (ref "J15") (pin "1") (pintype "power_in"))
      (node (ref "J9") (pin "1") (pintype "power_in"))
      (node (ref "P13") (pin "1") (pinfunction "1_1") (pintype "passive"))
      (node (ref "P14") (pin "1") (pinfunction "1_1") (pintype "passive"))
      (node (ref "P8") (pin "4") (pinfunction "4_4") (pintype "passive"))
      (node (ref "R12") (pin "1") (pinfunction "1_1") (pintype "passive"))
      (node (ref "R27") (pin "1") (pinfunction "1_1") (pintype "passive"))
      (node (ref "R32") (pin "1") (pinfunction "1_1") (pintype "passive"))
      (node (ref "R5") (pin "1") (pinfunction "1_1") (pintype "passive"))
      (node (ref "S1") (pin "1") (pinfunction "A0_1") (pintype "passive"))
      (node (ref "S1") (pin "2") (pinfunction "A1_2") (pintype "passive"))
      (node (ref "S8") (pin "1") (pinfunction "A0_1") (pintype "passive"))
      (node (ref "S8") (pin "2") (pinfunction "A1_2") (pintype "passive"))
      (node (ref "S9") (pin "1") (pinfunction "A0_1") (pintype "passive"))
      (node (ref "S9") (pin "2") (pinfunction "A1_2") (pintype "passive"))
      (node (ref "SW2") (pin "3") (pinfunction "B0_3") (pintype "passive"))
      (node (ref "SW2") (pin "4") (pinfunction "B1_4") (pintype "passive"))
      (node (ref "SW3") (pin "3") (pinfunction "B0_3") (pintype "passive"))
      (node (ref "SW3") (pin "4") (pinfunction "B1_4") (pintype "passive"))
      (node (ref "SW4") (pin "3") (pinfunction "B0_3") (pintype "passive"))
      (node (ref "SW4") (pin "4") (pinfunction "B1_4") (pintype "passive"))
      (node (ref "U1") (pin "6") (pinfunction "GND_6") (pintype "power_in"))
      (node (ref "U10") (pin "2") (pinfunction "Solar-_2") (pintype "power_in"))
      (node (ref "U11") (pin "2") (pinfunction "GND_2") (pintype "power_in"))
      (node (ref "U12") (pin "3") (pinfunction "GND_3") (pintype "passive"))
      (node (ref "U13") (pin "5") (pinfunction "GND_5") (pintype "power_in"))
      (node (ref "U14") (pin "2") (pinfunction "GND_2") (pintype "power_in"))
      (node (ref "U15") (pin "1") (pinfunction "GND_1") (pintype "power_in"))
      (node (ref "U16") (pin "1") (pinfunction "GND_1") (pintype "power_in"))
      (node (ref "U17") (pin "1") (pinfunction "GND_1") (pintype "power_in"))
      (node (ref "U18") (pin "1") (pinfunction "GND_1") (pintype "power_in"))
      (node (ref "U19") (pin "GND") (pinfunction "GND_GND") (pintype "power_in"))
      (node (ref "U2") (pin "4") (pinfunction "GND_4") (pintype "passive"))
      (node (ref "U3") (pin "C2") (pinfunction "GND_C2") (pintype "power_in"))
      (node (ref "U4") (pin "2") (pinfunction "Solar-_2") (pintype "power_in"))
      (node (ref "U5") (pin "1") (pinfunction "A0_1") (pintype "passive"))
      (node (ref "U5") (pin "2") (pinfunction "A1_2") (pintype "passive"))
      (node (ref "U5") (pin "3") (pinfunction "A2_3") (pintype "passive"))
      (node (ref "U5") (pin "4") (pinfunction "Vss_4") (pintype "passive"))
      (node (ref "U6") (pin "21") (pinfunction "GND_21") (pintype "power_in"))
      (node (ref "U6") (pin "3") (pinfunction "GND_3") (pintype "power_in"))
      (node (ref "U6") (pin "5") (pinfunction "GND_5") (pintype "power_in"))
      (node (ref "U7") (pin "OUT-") (pinfunction "OUT-_OUT-") (pintype "power_in"))
      (node (ref "X1") (pin "9") (pinfunction "GND_9") (pintype "power_in"))
      (node (ref "Z1") (pin "1") (pinfunction "1_1") (pintype "power_in"))
      (node (ref "Z1") (pin "10") (pinfunction "10_10") (pintype "power_in"))
      (node (ref "Z1") (pin "2") (pinfunction "2_2") (pintype "power_in"))
      (node (ref "Z1") (pin "3") (pinfunction "3_3") (pintype "power_in"))
      (node (ref "Z1") (pin "4") (pinfunction "4_4") (pintype "power_in"))
      (node (ref "Z1") (pin "5") (pinfunction "5_5") (pintype "power_in"))
      (node (ref "Z1") (pin "6") (pinfunction "6_6") (pintype "power_in"))
      (node (ref "Z1") (pin "7") (pinfunction "7_7") (pintype "power_in"))
      (node (ref "Z1") (pin "8") (pinfunction "8_8") (pintype "power_in"))
      (node (ref "Z1") (pin "9") (pinfunction "9_9") (pintype "power_in"))
      (node (ref "Z2") (pin "1") (pinfunction "1_1") (pintype "power_in"))
      (node (ref "Z2") (pin "10") (pinfunction "10_10") (pintype "power_in"))
      (node (ref "Z2") (pin "2") (pinfunction "2_2") (pintype "power_in"))
      (node (ref "Z2") (pin "3") (pinfunction "3_3") (pintype "power_in"))
      (node (ref "Z2") (pin "4") (pinfunction "4_4") (pintype "power_in"))
      (node (ref "Z2") (pin "5") (pinfunction "5_5") (pintype "power_in"))
      (node (ref "Z2") (pin "6") (pinfunction "6_6") (pintype "power_in"))
      (node (ref "Z2") (pin "7") (pinfunction "7_7") (pintype "power_in"))
      (node (ref "Z2") (pin "8") (pinfunction "8_8") (pintype "power_in"))
      (node (ref "Z2") (pin "9") (pinfunction "9_9") (pintype "power_in"))
    )
    (net (code "43") (name "Net-(C4-Pad2)") (class "Default")
      (node (ref "C4") (pin "2") (pinfunction "2_2") (pintype "passive"))
      (node (ref "P3") (pin "1") (pinfunction "1_1") (pintype "passive"))
      (node (ref "R2") (pin "2") (pinfunction "2_2") (pintype "passive"))
    )
    (net (code "44") (name "Net-(D1-K)") (class "Default")
      (node (ref "D1") (pin "2") (pinfunction "K_2") (pintype "passive"))
      (node (ref "F2") (pin "2") (pinfunction "2_2") (pintype "passive"))
      (node (ref "R1") (pin "1") (pinfunction "1_1") (pintype "passive"))
      (node (ref "R2") (pin "1") (pinfunction "1_1") (pintype "passive"))
      (node (ref "R34") (pin "1") (pinfunction "1_1") (pintype "power_in"))
      (node (ref "U1") (pin "12") (pinfunction "SENSE+_12") (pintype "power_in"))
    )
    (net (code "45") (name "Net-(D2-Pad+)") (class "Default")
      (node (ref "D2") (pin "+") (pinfunction "+_+") (pintype "passive"))
      (node (ref "R3") (pin "2") (pinfunction "2_2") (pintype "passive"))
    )
    (net (code "46") (name "Net-(D4-Pad+)") (class "Default")
      (node (ref "D4") (pin "+") (pinfunction "+_+") (pintype "passive"))
      (node (ref "R9") (pin "2") (pinfunction "2_2") (pintype "passive"))
    )
    (net (code "47") (name "Net-(D5-Pad+)") (class "Default")
      (node (ref "D5") (pin "+") (pinfunction "+_+") (pintype "passive"))
      (node (ref "R10") (pin "1") (pinfunction "1_1") (pintype "passive"))
    )
    (net (code "48") (name "Net-(D6-Pad+)") (class "Default")
      (node (ref "D6") (pin "+") (pinfunction "+_+") (pintype "passive"))
      (node (ref "R21") (pin "1") (pinfunction "1_1") (pintype "passive"))
    )
    (net (code "49") (name "Net-(D7-Pad+)") (class "Default")
      (node (ref "D7") (pin "+") (pinfunction "+_+") (pintype "passive"))
      (node (ref "R24") (pin "1") (pinfunction "1_1") (pintype "passive"))
    )
    (net (code "50") (name "Net-(D8-Pad+)") (class "Default")
      (node (ref "D8") (pin "+") (pinfunction "+_+") (pintype "passive"))
      (node (ref "R31") (pin "1") (pinfunction "1_1") (pintype "passive"))
    )
    (net (code "51") (name "Net-(J1-Pad1)") (class "Default")
      (node (ref "J1") (pin "1") (pinfunction "1_1") (pintype "passive"))
      (node (ref "P3") (pin "5") (pinfunction "5_5") (pintype "passive"))
    )
    (net (code "52") (name "Net-(J5-Pad1)") (class "Default")
      (node (ref "J5") (pin "1") (pinfunction "1_1") (pintype "power_in"))
      (node (ref "R10") (pin "2") (pinfunction "2_2") (pintype "passive"))
    )
    (net (code "53") (name "Net-(J15-Pad2)") (class "Default")
      (node (ref "J15") (pin "2") (pinfunction "2_2") (pintype "power_in"))
      (node (ref "U19") (pin "DATA") (pinfunction "DATA_DATA") (pintype "power_in"))
    )
    (net (code "54") (name "Net-(P12-Pad3)") (class "Default")
      (node (ref "P12") (pin "3") (pinfunction "3_3") (pintype "passive"))
      (node (ref "R23") (pin "2") (pinfunction "2_2") (pintype "passive"))
    )
    (net (code "55") (name "Net-(P15-T+)") (class "Default")
      (node (ref "C19") (pin "2") (pinfunction "2_2") (pintype "passive"))
      (node (ref "P15") (pin "2") (pinfunction "T+_2") (pintype "power_in"))
      (node (ref "U18") (pin "3") (pinfunction "T+_3") (pintype "power_in"))
    )
    (net (code "56") (name "Net-(P15-T-)") (class "Default")
      (node (ref "C19") (pin "1") (pinfunction "1_1") (pintype "passive"))
      (node (ref "P15") (pin "1") (pinfunction "T-_1") (pintype "power_in"))
      (node (ref "U18") (pin "2") (pinfunction "T-_2") (pintype "power_in"))
    )
    (net (code "57") (name "Net-(R30-Pad1)") (class "Default")
      (node (ref "R30") (pin "1") (pinfunction "1_1") (pintype "passive"))
      (node (ref "R32") (pin "2") (pinfunction "2_2") (pintype "passive"))
    )
    (net (code "58") (name "Net-(U1-ADR0)") (class "Default")
      (node (ref "J10") (pin "2") (pinfunction "2_2") (pintype "power_in"))
      (node (ref "U1") (pin "4") (pinfunction "ADR0_4") (pintype "power_in"))
    )
    (net (code "59") (name "Net-(U1-ADR1)") (class "Default")
      (node (ref "J9") (pin "2") (pinfunction "2_2") (pintype "power_in"))
      (node (ref "U1") (pin "3") (pinfunction "ADR1_3") (pintype "power_in"))
    )
    (net (code "60") (name "Net-(U1-SDAO)") (class "Default")
      (node (ref "J11") (pin "1") (pintype "power_in"))
      (node (ref "U1") (pin "9") (pinfunction "SDAO_9") (pintype "power_in"))
    )
    (net (code "61") (name "Net-(U1-SENSE-)") (class "Default")
      (node (ref "F3") (pin "1") (pinfunction "1_1") (pintype "passive"))
      (node (ref "R1") (pin "2") (pinfunction "2_2") (pintype "passive"))
      (node (ref "R34") (pin "2") (pinfunction "2_2") (pintype "power_in"))
      (node (ref "U1") (pin "11") (pinfunction "SENSE-_11") (pintype "power_in"))
    )
    (net (code "62") (name "Net-(U1-VDD)") (class "Default")
      (node (ref "C3") (pin "2") (pinfunction "2_2") (pintype "passive"))
      (node (ref "P3") (pin "2") (pinfunction "2_2") (pintype "passive"))
      (node (ref "P3") (pin "4") (pinfunction "4_4") (pintype "passive"))
      (node (ref "P3") (pin "6") (pinfunction "6_6") (pintype "passive"))
      (node (ref "U1") (pin "1") (pinfunction "VDD_1") (pintype "power_in"))
    )
    (net (code "63") (name "Net-(U2-VBAT)") (class "Default")
      (node (ref "Cell1") (pin "1+") (pinfunction "+Ve_1+") (pintype "passive"))
      (node (ref "Cell1") (pin "2+") (pinfunction "+Ve_2+") (pintype "passive"))
      (node (ref "U2") (pin "3") (pinfunction "VBAT_3") (pintype "power_in"))
    )
    (net (code "64") (name "Net-(U2-X1)") (class "Default")
      (node (ref "Q1") (pin "1") (pinfunction "1_1") (pintype "passive"))
      (node (ref "U2") (pin "1") (pinfunction "X1_1") (pintype "input"))
    )
    (net (code "65") (name "Net-(U2-X2)") (class "Default")
      (node (ref "Q1") (pin "2") (pinfunction "2_2") (pintype "passive"))
      (node (ref "U2") (pin "2") (pinfunction "X2_2") (pintype "output"))
    )
    (net (code "66") (name "Net-(U6-AREF)") (class "Default")
      (node (ref "C9") (pin "2") (pinfunction "2_2") (pintype "passive"))
      (node (ref "U6") (pin "20") (pinfunction "AREF_20") (pintype "passive"))
    )
    (net (code "67") (name "Net-(U11-DC-Out)") (class "Default")
      (node (ref "J6") (pin "1") (pinfunction "1_1") (pintype "power_in"))
      (node (ref "U11") (pin "4") (pinfunction "DC-Out_4") (pintype "power_in"))
    )
    (net (code "68") (name "Net-(U13-FILTER)") (class "Default")
      (node (ref "C14") (pin "2") (pinfunction "2_2") (pintype "passive"))
      (node (ref "U13") (pin "6") (pinfunction "FILTER_6") (pintype "passive"))
    )
    (net (code "69") (name "Net-(U13-I+_0)") (class "Default")
      (node (ref "F4") (pin "2") (pinfunction "2_2") (pintype "passive"))
      (node (ref "U13") (pin "1") (pinfunction "I+_0_1") (pintype "passive"))
      (node (ref "U13") (pin "2") (pinfunction "I+_1_2") (pintype "passive"))
    )
    (net (code "70") (name "Net-(U13-I-_0)") (class "Default")
      (node (ref "F5") (pin "1") (pinfunction "1_1") (pintype "passive"))
      (node (ref "U13") (pin "3") (pinfunction "I-_0_3") (pintype "passive"))
      (node (ref "U13") (pin "4") (pinfunction "I-_1_4") (pintype "passive"))
    )
    (net (code "71") (name "Net-(X1-RXD)") (class "Default")
      (node (ref "R23") (pin "1") (pinfunction "1_1") (pintype "passive"))
      (node (ref "R30") (pin "2") (pinfunction "2_2") (pintype "passive"))
      (node (ref "X1") (pin "15") (pinfunction "RXD_15") (pintype "passive"))
    )
    (net (code "72") (name "Net-(X1-TXD)") (class "Default")
      (node (ref "P12") (pin "1") (pinfunction "1_1") (pintype "passive"))
      (node (ref "X1") (pin "16") (pinfunction "TXD_16") (pintype "output"))
    )
    (net (code "73") (name "VCC-3V3") (class "Default")
      (node (ref "C17") (pin "2") (pinfunction "2_2") (pintype "passive"))
      (node (ref "C18") (pin "+") (pinfunction "+_+") (pintype "passive"))
      (node (ref "R21") (pin "2") (pinfunction "2_2") (pintype "passive"))
      (node (ref "R24") (pin "2") (pinfunction "2_2") (pintype "passive"))
      (node (ref "R25") (pin "2") (pinfunction "2_2") (pintype "passive"))
      (node (ref "R26") (pin "2") (pinfunction "2_2") (pintype "passive"))
      (node (ref "R33") (pin "2") (pinfunction "2_2") (pintype "passive"))
      (node (ref "U17") (pin "2") (pinfunction "Vout_2") (pintype "power_in"))
      (node (ref "X1") (pin "8") (pinfunction "VCC_8") (pintype "power_in"))
    )
    (net (code "74") (name "VCC-5V") (class "Default")
      (node (ref "C10") (pin "+") (pinfunction "+_+") (pintype "passive"))
      (node (ref "C11") (pin "2") (pinfunction "2_2") (pintype "passive"))
      (node (ref "C22") (pin "+") (pinfunction "+_+") (pintype "passive"))
      (node (ref "C7") (pin "2") (pinfunction "2_2") (pintype "passive"))
      (node (ref "J10") (pin "3") (pinfunction "3_3") (pintype "power_in"))
      (node (ref "J12") (pin "1") (pintype "power_in"))
      (node (ref "J5") (pin "2") (pinfunction "2_2") (pintype "power_in"))
      (node (ref "J9") (pin "3") (pinfunction "3_3") (pintype "power_in"))
      (node (ref "P3") (pin "3") (pinfunction "3_3") (pintype "passive"))
      (node (ref "P8") (pin "6") (pinfunction "6_6") (pintype "passive"))
      (node (ref "R3") (pin "1") (pinfunction "1_1") (pintype "passive"))
      (node (ref "R4") (pin "2") (pinfunction "2_2") (pintype "passive"))
      (node (ref "R7") (pin "2") (pinfunction "2_2") (pintype "passive"))
      (node (ref "R8") (pin "2") (pinfunction "2_2") (pintype "passive"))
      (node (ref "U1") (pin "2") (pinfunction "INTVcc_2") (pintype "power_in"))
      (node (ref "U13") (pin "8") (pinfunction "VCC_8") (pintype "power_in"))
      (node (ref "U3") (pin "A1") (pinfunction "VIN_A1") (pintype "power_in"))
      (node (ref "U3") (pin "B1") (pinfunction "VIN_B1") (pintype "power_in"))
      (node (ref "U6") (pin "18") (pinfunction "AVCC_18") (pintype "power_in"))
      (node (ref "U6") (pin "4") (pinfunction "VCC_4") (pintype "power_in"))
      (node (ref "U6") (pin "6") (pinfunction "VCC_6") (pintype "power_in"))
      (node (ref "U7") (pin "OUT+") (pinfunction "OUT+_OUT+") (pintype "power_in"))
    )
    (net (code "75") (name "VCC-5V-EN") (class "Default")
      (node (ref "C1") (pin "2") (pinfunction "2_2") (pintype "passive"))
      (node (ref "C15") (pin "+") (pinfunction "+_+") (pintype "passive"))
      (node (ref "C16") (pin "2") (pinfunction "2_2") (pintype "passive"))
      (node (ref "C2") (pin "+") (pinfunction "+_+") (pintype "passive"))
      (node (ref "C20") (pin "+") (pinfunction "+_+") (pintype "passive"))
      (node (ref "C21") (pin "2") (pinfunction "2_2") (pintype "passive"))
      (node (ref "C5") (pin "+") (pinfunction "+_+") (pintype "passive"))
      (node (ref "C6") (pin "2") (pinfunction "2_2") (pintype "passive"))
      (node (ref "CN1") (pin "3") (pinfunction "3_3") (pintype "passive"))
      (node (ref "D3") (pin "2") (pinfunction "K_2") (pintype "passive"))
      (node (ref "J12") (pin "3") (pinfunction "3_3") (pintype "power_in"))
      (node (ref "J13") (pin "1") (pintype "power_in"))
      (node (ref "J14") (pin "1") (pintype "power_in"))
      (node (ref "J15") (pin "3") (pinfunction "3_3") (pintype "power_in"))
      (node (ref "R15") (pin "2") (pinfunction "2_2") (pintype "passive"))
      (node (ref "R16") (pin "2") (pinfunction "2_2") (pintype "passive"))
      (node (ref "R17") (pin "2") (pinfunction "2_2") (pintype "passive"))
      (node (ref "R18") (pin "1") (pinfunction "1_1") (pintype "passive"))
      (node (ref "R19") (pin "1") (pinfunction "1_1") (pintype "passive"))
      (node (ref "R20") (pin "2") (pinfunction "2_2") (pintype "passive"))
      (node (ref "R28") (pin "1") (pinfunction "1_1") (pintype "passive"))
      (node (ref "R29") (pin "1") (pinfunction "1_1") (pintype "passive"))
      (node (ref "R31") (pin "2") (pinfunction "2_2") (pintype "passive"))
      (node (ref "R6") (pin "1") (pinfunction "1_1") (pintype "passive"))
      (node (ref "U14") (pin "1") (pinfunction "VCC_1") (pintype "power_in"))
      (node (ref "U15") (pin "3") (pinfunction "VDD_3") (pintype "power_in"))
      (node (ref "U16") (pin "3") (pinfunction "VDD_3") (pintype "power_in"))
      (node (ref "U17") (pin "3") (pinfunction "Vin_3") (pintype "power_in"))
      (node (ref "U18") (pin "4") (pinfunction "Vcc_4") (pintype "power_in"))
      (node (ref "U19") (pin "VDD") (pinfunction "VDD_VDD") (pintype "power_in"))
      (node (ref "U2") (pin "8") (pinfunction "VCC_8") (pintype "power_in"))
      (node (ref "U3") (pin "A2") (pinfunction "VOUT_A2") (pintype "power_in"))
      (node (ref "U3") (pin "B2") (pinfunction "VOUT_B2") (pintype "power_in"))
      (node (ref "U5") (pin "8") (pinfunction "VCC_8") (pintype "passive"))
      (node (ref "Z1") (pin "41") (pinfunction "41_41") (pintype "power_in"))
      (node (ref "Z1") (pin "42") (pinfunction "42_42") (pintype "power_in"))
      (node (ref "Z1") (pin "43") (pinfunction "43_43") (pintype "power_in"))
      (node (ref "Z1") (pin "44") (pinfunction "44_44") (pintype "power_in"))
      (node (ref "Z1") (pin "45") (pinfunction "45_45") (pintype "power_in"))
      (node (ref "Z1") (pin "46") (pinfunction "46_46") (pintype "power_in"))
      (node (ref "Z1") (pin "47") (pinfunction "47_47") (pintype "power_in"))
      (node (ref "Z1") (pin "48") (pinfunction "48_48") (pintype "power_in"))
      (node (ref "Z1") (pin "49") (pinfunction "49_49") (pintype "power_in"))
      (node (ref "Z1") (pin "50") (pinfunction "50_50") (pintype "power_in"))
      (node (ref "Z2") (pin "41") (pinfunction "41_41") (pintype "power_in"))
      (node (ref "Z2") (pin "42") (pinfunction "42_42") (pintype "power_in"))
      (node (ref "Z2") (pin "43") (pinfunction "43_43") (pintype "power_in"))
      (node (ref "Z2") (pin "44") (pinfunction "44_44") (pintype "power_in"))
      (node (ref "Z2") (pin "45") (pinfunction "45_45") (pintype "power_in"))
      (node (ref "Z2") (pin "46") (pinfunction "46_46") (pintype "power_in"))
      (node (ref "Z2") (pin "47") (pinfunction "47_47") (pintype "power_in"))
      (node (ref "Z2") (pin "48") (pinfunction "48_48") (pintype "power_in"))
      (node (ref "Z2") (pin "49") (pinfunction "49_49") (pintype "power_in"))
      (node (ref "Z2") (pin "50") (pinfunction "50_50") (pintype "power_in"))
    )
    (net (code "76") (name "unconnected-(J11-Pad3)") (class "Default")
      (node (ref "J11") (pin "3") (pinfunction "3_3") (pintype "power_in+no_connect"))
    )
    (net (code "77") (name "unconnected-(U2-SQW{slash}OUT-Pad7)") (class "Default")
      (node (ref "U2") (pin "7") (pinfunction "SQW/OUT_7") (pintype "output+no_connect"))
    )
    (net (code "78") (name "unconnected-(U5-WP-Pad7)") (class "Default")
      (node (ref "U5") (pin "7") (pinfunction "WP_7") (pintype "passive+no_connect"))
    )
    (net (code "79") (name "unconnected-(U12-QST-Pad5)") (class "Default")
      (node (ref "U12") (pin "5") (pinfunction "QST_5") (pintype "passive+no_connect"))
    )
    (net (code "80") (name "unconnected-(U18-N.C.-Pad8)") (class "Default")
      (node (ref "U18") (pin "8") (pinfunction "N.C._8") (pintype "power_in+no_connect"))
    )
    (net (code "81") (name "unconnected-(U19-PadNC)") (class "Default")
      (node (ref "U19") (pin "NC") (pinfunction "NC_NC") (pintype "power_in+no_connect"))
    )
    (net (code "82") (name "unconnected-(X1-ADC-Pad2)") (class "Default")
      (node (ref "X1") (pin "2") (pinfunction "ADC_2") (pintype "passive"))
    )
    (net (code "83") (name "unconnected-(X1-GPIO4-Pad14)") (class "Default")
      (node (ref "X1") (pin "14") (pinfunction "GPIO4_14") (pintype "passive"))
    )
    (net (code "84") (name "unconnected-(X1-GPIO5-Pad13)") (class "Default")
      (node (ref "X1") (pin "13") (pinfunction "GPIO5_13") (pintype "passive"))
    )
    (net (code "85") (name "unconnected-(X1-GPIO12-Pad6)") (class "Default")
      (node (ref "X1") (pin "6") (pinfunction "GPIO12_6") (pintype "passive"))
    )
    (net (code "86") (name "unconnected-(X1-GPIO13-Pad7)") (class "Default")
      (node (ref "X1") (pin "7") (pinfunction "GPIO13_7") (pintype "passive"))
    )
    (net (code "87") (name "unconnected-(X1-GPIO14-Pad5)") (class "Default")
      (node (ref "X1") (pin "5") (pinfunction "GPIO14_5") (pintype "passive"))
    )
    (net (code "88") (name "unconnected-(X1-GPIO16-Pad4)") (class "Default")
      (node (ref "X1") (pin "4") (pinfunction "GPIO16_4") (pintype "passive"))
    )
    (net (code "89") (name "unconnected-(Z1-Pad11)") (class "Default")
      (node (ref "Z1") (pin "11") (pinfunction "11_11") (pintype "power_in"))
    )
    (net (code "90") (name "unconnected-(Z1-Pad12)") (class "Default")
      (node (ref "Z1") (pin "12") (pinfunction "12_12") (pintype "power_in"))
    )
    (net (code "91") (name "unconnected-(Z1-Pad13)") (class "Default")
      (node (ref "Z1") (pin "13") (pinfunction "13_13") (pintype "power_in"))
    )
    (net (code "92") (name "unconnected-(Z1-Pad14)") (class "Default")
      (node (ref "Z1") (pin "14") (pinfunction "14_14") (pintype "power_in"))
    )
    (net (code "93") (name "unconnected-(Z1-Pad15)") (class "Default")
      (node (ref "Z1") (pin "15") (pinfunction "15_15") (pintype "power_in"))
    )
    (net (code "94") (name "unconnected-(Z1-Pad16)") (class "Default")
      (node (ref "Z1") (pin "16") (pinfunction "16_16") (pintype "power_in"))
    )
    (net (code "95") (name "unconnected-(Z1-Pad17)") (class "Default")
      (node (ref "Z1") (pin "17") (pinfunction "17_17") (pintype "power_in"))
    )
    (net (code "96") (name "unconnected-(Z1-Pad18)") (class "Default")
      (node (ref "Z1") (pin "18") (pinfunction "18_18") (pintype "power_in"))
    )
    (net (code "97") (name "unconnected-(Z1-Pad19)") (class "Default")
      (node (ref "Z1") (pin "19") (pinfunction "19_19") (pintype "power_in"))
    )
    (net (code "98") (name "unconnected-(Z1-Pad20)") (class "Default")
      (node (ref "Z1") (pin "20") (pinfunction "20_20") (pintype "power_in"))
    )
    (net (code "99") (name "unconnected-(Z1-Pad21)") (class "Default")
      (node (ref "Z1") (pin "21") (pinfunction "21_21") (pintype "power_in"))
    )
    (net (code "100") (name "unconnected-(Z1-Pad22)") (class "Default")
      (node (ref "Z1") (pin "22") (pinfunction "22_22") (pintype "power_in"))
    )
    (net (code "101") (name "unconnected-(Z1-Pad23)") (class "Default")
      (node (ref "Z1") (pin "23") (pinfunction "23_23") (pintype "power_in"))
    )
    (net (code "102") (name "unconnected-(Z1-Pad24)") (class "Default")
      (node (ref "Z1") (pin "24") (pinfunction "24_24") (pintype "power_in"))
    )
    (net (code "103") (name "unconnected-(Z1-Pad25)") (class "Default")
      (node (ref "Z1") (pin "25") (pinfunction "25_25") (pintype "power_in"))
    )
    (net (code "104") (name "unconnected-(Z1-Pad26)") (class "Default")
      (node (ref "Z1") (pin "26") (pinfunction "26_26") (pintype "power_in"))
    )
    (net (code "105") (name "unconnected-(Z1-Pad27)") (class "Default")
      (node (ref "Z1") (pin "27") (pinfunction "27_27") (pintype "power_in"))
    )
    (net (code "106") (name "unconnected-(Z1-Pad28)") (class "Default")
      (node (ref "Z1") (pin "28") (pinfunction "28_28") (pintype "power_in"))
    )
    (net (code "107") (name "unconnected-(Z1-Pad29)") (class "Default")
      (node (ref "Z1") (pin "29") (pinfunction "29_29") (pintype "power_in"))
    )
    (net (code "108") (name "unconnected-(Z1-Pad30)") (class "Default")
      (node (ref "Z1") (pin "30") (pinfunction "30_30") (pintype "power_in"))
    )
    (net (code "109") (name "unconnected-(Z1-Pad31)") (class "Default")
      (node (ref "Z1") (pin "31") (pinfunction "31_31") (pintype "power_in"))
    )
    (net (code "110") (name "unconnected-(Z1-Pad32)") (class "Default")
      (node (ref "Z1") (pin "32") (pinfunction "32_32") (pintype "power_in"))
    )
    (net (code "111") (name "unconnected-(Z1-Pad33)") (class "Default")
      (node (ref "Z1") (pin "33") (pinfunction "33_33") (pintype "power_in"))
    )
    (net (code "112") (name "unconnected-(Z1-Pad34)") (class "Default")
      (node (ref "Z1") (pin "34") (pinfunction "34_34") (pintype "power_in"))
    )
    (net (code "113") (name "unconnected-(Z1-Pad35)") (class "Default")
      (node (ref "Z1") (pin "35") (pinfunction "35_35") (pintype "power_in"))
    )
    (net (code "114") (name "unconnected-(Z1-Pad36)") (class "Default")
      (node (ref "Z1") (pin "36") (pinfunction "36_36") (pintype "power_in"))
    )
    (net (code "115") (name "unconnected-(Z1-Pad37)") (class "Default")
      (node (ref "Z1") (pin "37") (pinfunction "37_37") (pintype "power_in"))
    )
    (net (code "116") (name "unconnected-(Z1-Pad38)") (class "Default")
      (node (ref "Z1") (pin "38") (pinfunction "38_38") (pintype "power_in"))
    )
    (net (code "117") (name "unconnected-(Z1-Pad39)") (class "Default")
      (node (ref "Z1") (pin "39") (pinfunction "39_39") (pintype "power_in"))
    )
    (net (code "118") (name "unconnected-(Z1-Pad40)") (class "Default")
      (node (ref "Z1") (pin "40") (pinfunction "40_40") (pintype "power_in"))
    )
    (net (code "119") (name "unconnected-(Z2-Pad11)") (class "Default")
      (node (ref "Z2") (pin "11") (pinfunction "11_11") (pintype "power_in"))
    )
    (net (code "120") (name "unconnected-(Z2-Pad12)") (class "Default")
      (node (ref "Z2") (pin "12") (pinfunction "12_12") (pintype "power_in"))
    )
    (net (code "121") (name "unconnected-(Z2-Pad13)") (class "Default")
      (node (ref "Z2") (pin "13") (pinfunction "13_13") (pintype "power_in"))
    )
    (net (code "122") (name "unconnected-(Z2-Pad14)") (class "Default")
      (node (ref "Z2") (pin "14") (pinfunction "14_14") (pintype "power_in"))
    )
    (net (code "123") (name "unconnected-(Z2-Pad15)") (class "Default")
      (node (ref "Z2") (pin "15") (pinfunction "15_15") (pintype "power_in"))
    )
    (net (code "124") (name "unconnected-(Z2-Pad16)") (class "Default")
      (node (ref "Z2") (pin "16") (pinfunction "16_16") (pintype "power_in"))
    )
    (net (code "125") (name "unconnected-(Z2-Pad17)") (class "Default")
      (node (ref "Z2") (pin "17") (pinfunction "17_17") (pintype "power_in"))
    )
    (net (code "126") (name "unconnected-(Z2-Pad18)") (class "Default")
      (node (ref "Z2") (pin "18") (pinfunction "18_18") (pintype "power_in"))
    )
    (net (code "127") (name "unconnected-(Z2-Pad19)") (class "Default")
      (node (ref "Z2") (pin "19") (pinfunction "19_19") (pintype "power_in"))
    )
    (net (code "128") (name "unconnected-(Z2-Pad20)") (class "Default")
      (node (ref "Z2") (pin "20") (pinfunction "20_20") (pintype "power_in"))
    )
    (net (code "129") (name "unconnected-(Z2-Pad21)") (class "Default")
      (node (ref "Z2") (pin "21") (pinfunction "21_21") (pintype "power_in"))
    )
    (net (code "130") (name "unconnected-(Z2-Pad22)") (class "Default")
      (node (ref "Z2") (pin "22") (pinfunction "22_22") (pintype "power_in"))
    )
    (net (code "131") (name "unconnected-(Z2-Pad23)") (class "Default")
      (node (ref "Z2") (pin "23") (pinfunction "23_23") (pintype "power_in"))
    )
    (net (code "132") (name "unconnected-(Z2-Pad24)") (class "Default")
      (node (ref "Z2") (pin "24") (pinfunction "24_24") (pintype "power_in"))
    )
    (net (code "133") (name "unconnected-(Z2-Pad25)") (class "Default")
      (node (ref "Z2") (pin "25") (pinfunction "25_25") (pintype "power_in"))
    )
    (net (code "134") (name "unconnected-(Z2-Pad26)") (class "Default")
      (node (ref "Z2") (pin "26") (pinfunction "26_26") (pintype "power_in"))
    )
    (net (code "135") (name "unconnected-(Z2-Pad27)") (class "Default")
      (node (ref "Z2") (pin "27") (pinfunction "27_27") (pintype "power_in"))
    )
    (net (code "136") (name "unconnected-(Z2-Pad28)") (class "Default")
      (node (ref "Z2") (pin "28") (pinfunction "28_28") (pintype "power_in"))
    )
    (net (code "137") (name "unconnected-(Z2-Pad29)") (class "Default")
      (node (ref "Z2") (pin "29") (pinfunction "29_29") (pintype "power_in"))
    )
    (net (code "138") (name "unconnected-(Z2-Pad30)") (class "Default")
      (node (ref "Z2") (pin "30") (pinfunction "30_30") (pintype "power_in"))
    )
    (net (code "139") (name "unconnected-(Z2-Pad31)") (class "Default")
      (node (ref "Z2") (pin "31") (pinfunction "31_31") (pintype "power_in"))
    )
    (net (code "140") (name "unconnected-(Z2-Pad32)") (class "Default")
      (node (ref "Z2") (pin "32") (pinfunction "32_32") (pintype "power_in"))
    )
    (net (code "141") (name "unconnected-(Z2-Pad33)") (class "Default")
      (node (ref "Z2") (pin "33") (pinfunction "33_33") (pintype "power_in"))
    )
    (net (code "142") (name "unconnected-(Z2-Pad34)") (class "Default")
      (node (ref "Z2") (pin "34") (pinfunction "34_34") (pintype "power_in"))
    )
    (net (code "143") (name "unconnected-(Z2-Pad35)") (class "Default")
      (node (ref "Z2") (pin "35") (pinfunction "35_35") (pintype "power_in"))
    )
    (net (code "144") (name "unconnected-(Z2-Pad36)") (class "Default")
      (node (ref "Z2") (pin "36") (pinfunction "36_36") (pintype "power_in"))
    )
    (net (code "145") (name "unconnected-(Z2-Pad37)") (class "Default")
      (node (ref "Z2") (pin "37") (pinfunction "37_37") (pintype "power_in"))
    )
    (net (code "146") (name "unconnected-(Z2-Pad38)") (class "Default")
      (node (ref "Z2") (pin "38") (pinfunction "38_38") (pintype "power_in"))
    )
    (net (code "147") (name "unconnected-(Z2-Pad39)") (class "Default")
      (node (ref "Z2") (pin "39") (pinfunction "39_39") (pintype "power_in"))
    )
    (net (code "148") (name "unconnected-(Z2-Pad40)") (class "Default")
      (node (ref "Z2") (pin "40") (pinfunction "40_40") (pintype "power_in"))
    )
  )
)
